# WiFi_Switch.net
KiCad netlist of a schematic drawn in EAGLE
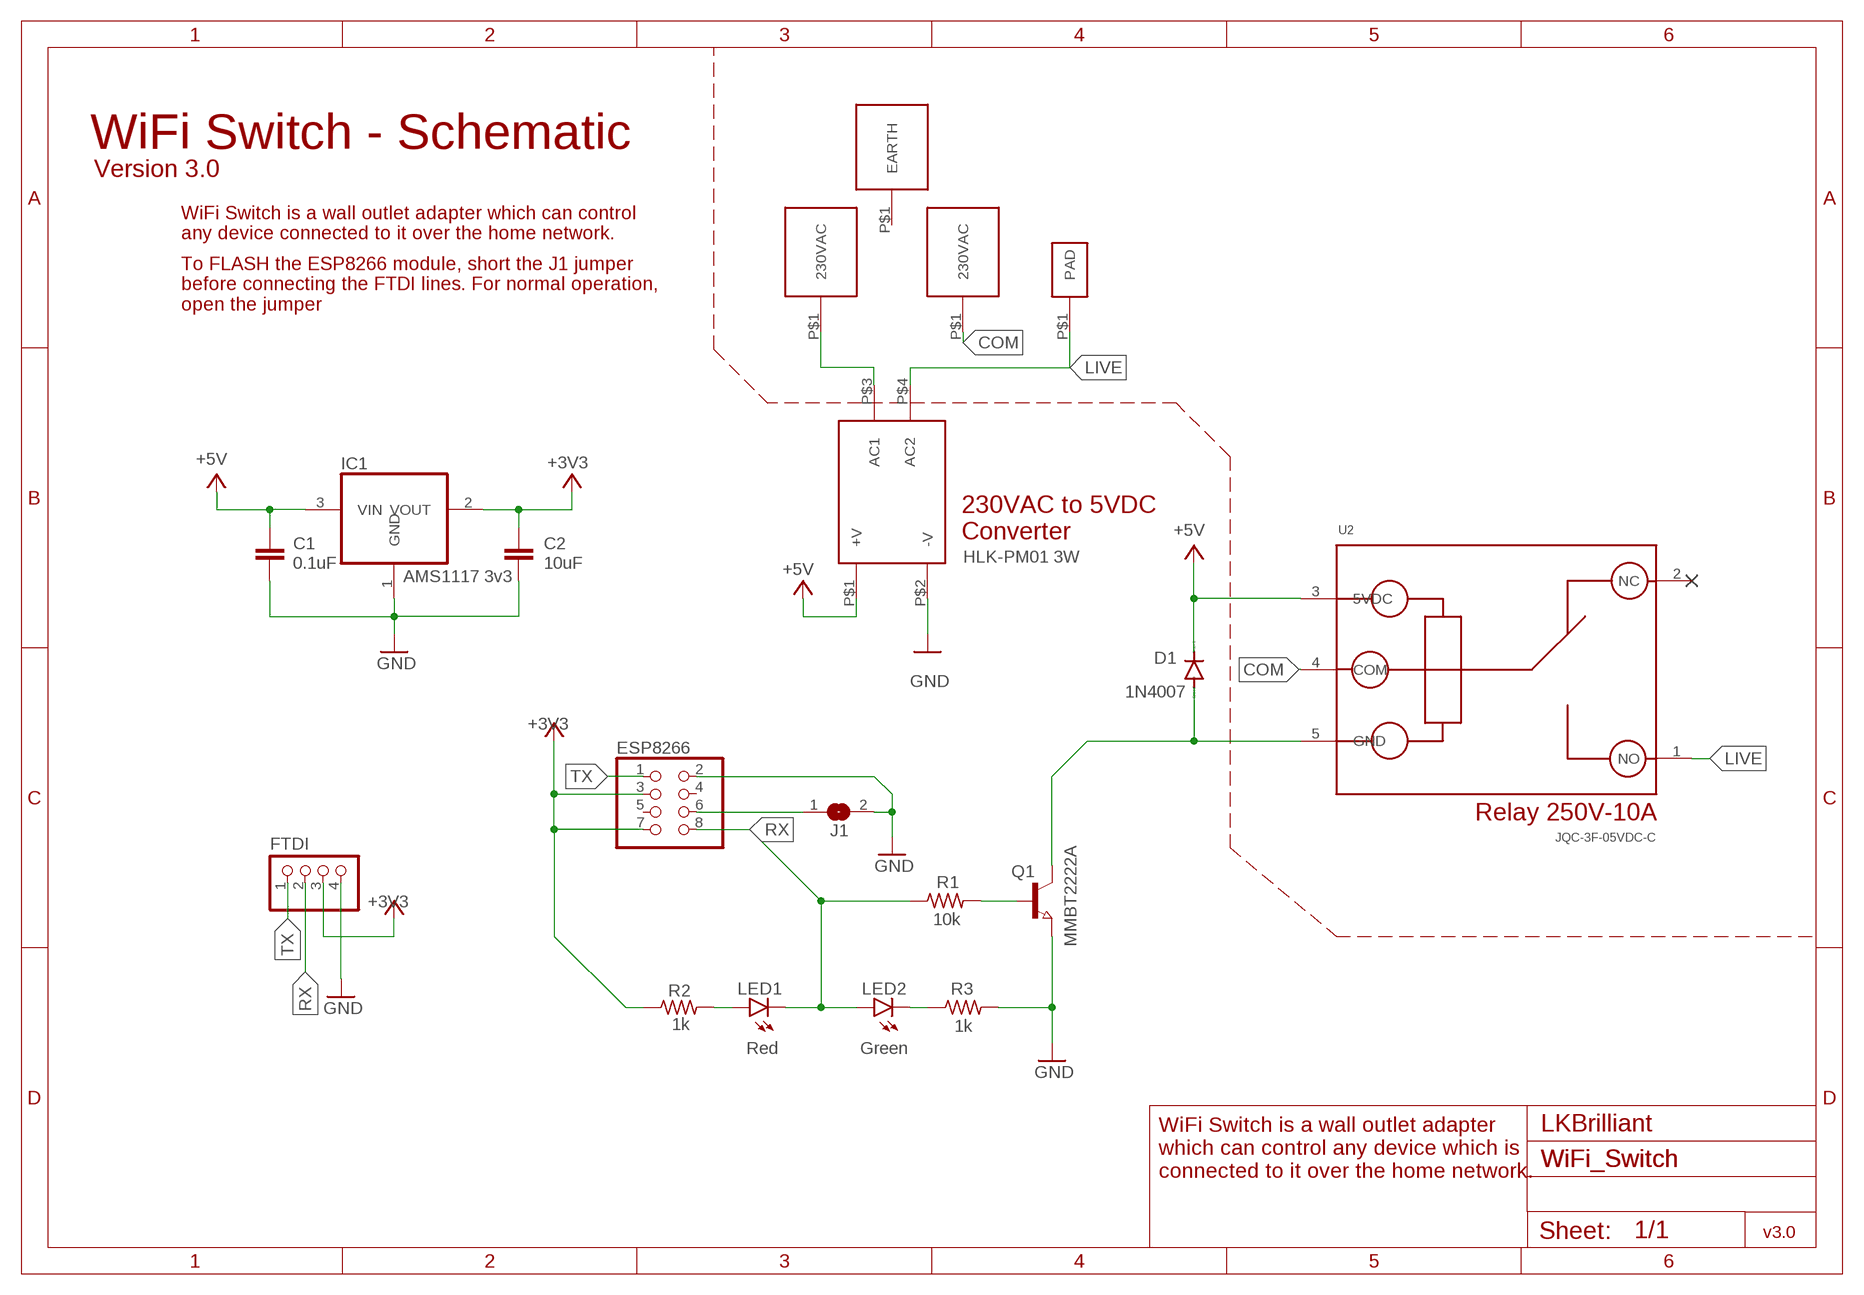
[diagram p0: schematic, sheet 1]

(export (version "E")
  (design (tool "Eeschema 10.0.6"))
  (components
    (comp (ref "C1")
      (value "0.1uF")
      (footprint "eagle-import:C0805")
      (libsource (lib "eagle-import") (part "C-EUC0805"))
    )
    (comp (ref "C2")
      (value "10uF")
      (footprint "eagle-import:C0805")
      (libsource (lib "eagle-import") (part "C-EUC0805"))
    )
    (comp (ref "D1")
      (value "1N4007")
      (footprint "eagle-import:DO214AC")
      (libsource (lib "eagle-import") (part "DIODE-DO214AC"))
    )
    (comp (ref "ESP8266")
      (value "PINHD-2X4")
      (footprint "eagle-import:2X04")
      (libsource (lib "eagle-import") (part "PINHD-2X4"))
    )
    (comp (ref "FTDI")
      (value "PINHD-1X4")
      (footprint "eagle-import:1X04")
      (libsource (lib "eagle-import") (part "PINHD-1X4"))
    )
    (comp (ref "IC1")
      (value "AMS1117 3v3")
      (footprint "eagle-import:SOT223")
      (fields (field (name "MPN") "REG1117"))
      (libsource (lib "eagle-import") (part "REG1117"))
    )
    (comp (ref "J1") (value "SJ") (footprint "eagle-import:SJ") (libsource (lib "eagle-import") (part "SJ")))
    (comp (ref "L")
      (value "230VAC_PAD")
      (footprint "eagle-import:11X9_SMD_PAD")
      (libsource (lib "eagle-import") (part "230VAC_PAD"))
    )
    (comp (ref "LED1")
      (value "Red")
      (footprint "eagle-import:CHIPLED_0603")
      (libsource (lib "eagle-import") (part "LEDCHIPLED_0603"))
    )
    (comp (ref "LED2")
      (value "Green")
      (footprint "eagle-import:CHIPLED_0603")
      (libsource (lib "eagle-import") (part "LEDCHIPLED_0603"))
    )
    (comp (ref "N")
      (value "230VAC_PAD")
      (footprint "eagle-import:11X9_SMD_PAD")
      (libsource (lib "eagle-import") (part "230VAC_PAD"))
    )
    (comp (ref "Q1")
      (value "MMBT2222A")
      (footprint "eagle-import:SOT23")
      (libsource (lib "eagle-import") (part "NPN-TRANSISTOR_SOT23"))
    )
    (comp (ref "R1")
      (value "10k")
      (footprint "eagle-import:R0805")
      (libsource (lib "eagle-import") (part "R-US_R0805"))
    )
    (comp (ref "R2")
      (value "1k")
      (footprint "eagle-import:R0805")
      (libsource (lib "eagle-import") (part "R-US_R0805"))
    )
    (comp (ref "R3")
      (value "1k")
      (footprint "eagle-import:R0805")
      (libsource (lib "eagle-import") (part "R-US_R0805"))
    )
    (comp (ref "U$4")
      (value "EARTH_PAD")
      (footprint "eagle-import:17X8_PAD")
      (libsource (lib "eagle-import") (part "EARTH_PAD"))
    )
    (comp (ref "U$5")
      (value "EXT_PAD")
      (footprint "eagle-import:4X2_PAD")
      (libsource (lib "eagle-import") (part "EXT_PAD"))
    )
    (comp (ref "U1")
      (value "230VAC/5VDC_CONVERTER")
      (footprint "eagle-import:REG_BLOCK")
      (libsource (lib "eagle-import") (part "230VAC/5VDC_CONVERTER"))
    )
    (comp (ref "U2")
      (value "JQC-3F-05VDC-C")
      (footprint "eagle-import:JQC-3F")
      (libsource (lib "eagle-import") (part "RELAY-JQC-3F"))
    )
  )
  (nets
    (net (code "1") (name "+3V3") (class "Default")
      (node (ref "C2") (pin "1") (pinfunction "1_1") (pintype "passive"))
      (node (ref "ESP8266") (pin "3") (pinfunction "3_3") (pintype "passive"))
      (node (ref "ESP8266") (pin "7") (pinfunction "7_7") (pintype "passive"))
      (node (ref "FTDI") (pin "3") (pinfunction "3_3") (pintype "passive"))
      (node (ref "IC1") (pin "2") (pinfunction "VOUT_2") (pintype "output"))
      (node (ref "R2") (pin "1") (pinfunction "1_1") (pintype "passive"))
    )
    (net (code "2") (name "+5V") (class "Default")
      (node (ref "C1") (pin "1") (pinfunction "1_1") (pintype "passive"))
      (node (ref "D1") (pin "C") (pinfunction "C_C") (pintype "passive"))
      (node (ref "IC1") (pin "3") (pinfunction "VIN_3") (pintype "input"))
      (node (ref "U1") (pin "P$1") (pinfunction "+V_P$1") (pintype "bidirectional"))
      (node (ref "U2") (pin "3") (pinfunction "5VDC_3") (pintype "bidirectional"))
    )
    (net (code "3") (name "COM") (class "Default")
      (node (ref "L") (pin "P$1") (pinfunction "230VAC_P$1") (pintype "bidirectional"))
      (node (ref "U2") (pin "4") (pinfunction "COM_4") (pintype "bidirectional"))
    )
    (net (code "4") (name "GND") (class "Default")
      (node (ref "C1") (pin "2") (pinfunction "2_2") (pintype "passive"))
      (node (ref "C2") (pin "2") (pinfunction "2_2") (pintype "passive"))
      (node (ref "ESP8266") (pin "2") (pinfunction "2_2") (pintype "passive"))
      (node (ref "FTDI") (pin "4") (pinfunction "4_4") (pintype "passive"))
      (node (ref "IC1") (pin "1") (pinfunction "GND_1") (pintype "power_in"))
      (node (ref "J1") (pin "2") (pinfunction "2_2") (pintype "passive"))
      (node (ref "Q1") (pin "2") (pinfunction "E_2") (pintype "passive"))
      (node (ref "R3") (pin "2") (pinfunction "2_2") (pintype "passive"))
      (node (ref "U1") (pin "P$2") (pinfunction "-V_P$2") (pintype "bidirectional"))
    )
    (net (code "5") (name "LIVE") (class "Default")
      (node (ref "U$5") (pin "P$1") (pinfunction "PAD_P$1") (pintype "bidirectional"))
      (node (ref "U1") (pin "P$4") (pinfunction "AC2_P$4") (pintype "bidirectional"))
      (node (ref "U2") (pin "1") (pinfunction "NO_1") (pintype "bidirectional"))
    )
    (net (code "6") (name "Net-(ESP8266-Pad6)") (class "Default")
      (node (ref "ESP8266") (pin "6") (pinfunction "6_6") (pintype "passive"))
      (node (ref "J1") (pin "1") (pinfunction "1_1") (pintype "passive"))
    )
    (net (code "7") (name "Net-(LED1-PadA)") (class "Default")
      (node (ref "LED1") (pin "A") (pinfunction "A_A") (pintype "passive"))
      (node (ref "R2") (pin "2") (pinfunction "2_2") (pintype "passive"))
    )
    (net (code "8") (name "Net-(LED2-PadC)") (class "Default")
      (node (ref "LED2") (pin "C") (pinfunction "C_C") (pintype "passive"))
      (node (ref "R3") (pin "1") (pinfunction "1_1") (pintype "passive"))
    )
    (net (code "9") (name "Net-(N-230VAC)") (class "Default")
      (node (ref "N") (pin "P$1") (pinfunction "230VAC_P$1") (pintype "bidirectional"))
      (node (ref "U1") (pin "P$3") (pinfunction "AC1_P$3") (pintype "bidirectional"))
    )
    (net (code "10") (name "Net-(Q1-B)") (class "Default")
      (node (ref "Q1") (pin "1") (pinfunction "B_1") (pintype "passive"))
      (node (ref "R1") (pin "2") (pinfunction "2_2") (pintype "passive"))
    )
    (net (code "11") (name "Net-(Q1-C)") (class "Default")
      (node (ref "D1") (pin "A") (pinfunction "A_A") (pintype "passive"))
      (node (ref "Q1") (pin "3") (pinfunction "C_3") (pintype "passive"))
      (node (ref "U2") (pin "5") (pinfunction "GND_5") (pintype "bidirectional"))
    )
    (net (code "12") (name "RX") (class "Default")
      (node (ref "ESP8266") (pin "8") (pinfunction "8_8") (pintype "passive"))
      (node (ref "FTDI") (pin "2") (pinfunction "2_2") (pintype "passive"))
      (node (ref "LED1") (pin "C") (pinfunction "C_C") (pintype "passive"))
      (node (ref "LED2") (pin "A") (pinfunction "A_A") (pintype "passive"))
      (node (ref "R1") (pin "1") (pinfunction "1_1") (pintype "passive"))
    )
    (net (code "13") (name "TX") (class "Default")
      (node (ref "ESP8266") (pin "1") (pinfunction "1_1") (pintype "passive"))
      (node (ref "FTDI") (pin "1") (pinfunction "1_1") (pintype "passive"))
    )
    (net (code "14") (name "unconnected-(ESP8266-Pad4)") (class "Default")
      (node (ref "ESP8266") (pin "4") (pinfunction "4_4") (pintype "passive"))
    )
    (net (code "15") (name "unconnected-(ESP8266-Pad5)") (class "Default")
      (node (ref "ESP8266") (pin "5") (pinfunction "5_5") (pintype "passive"))
    )
    (net (code "16") (name "unconnected-(U$4-EARTH-PadP$1)") (class "Default")
      (node (ref "U$4") (pin "P$1") (pinfunction "EARTH_P$1") (pintype "bidirectional"))
    )
    (net (code "17") (name "unconnected-(U2-NC-Pad2)") (class "Default")
      (node (ref "U2") (pin "2") (pinfunction "NC_2") (pintype "bidirectional"))
    )
  )
)
